# LTC4222.net
KiCad netlist of a schematic drawn in EAGLE
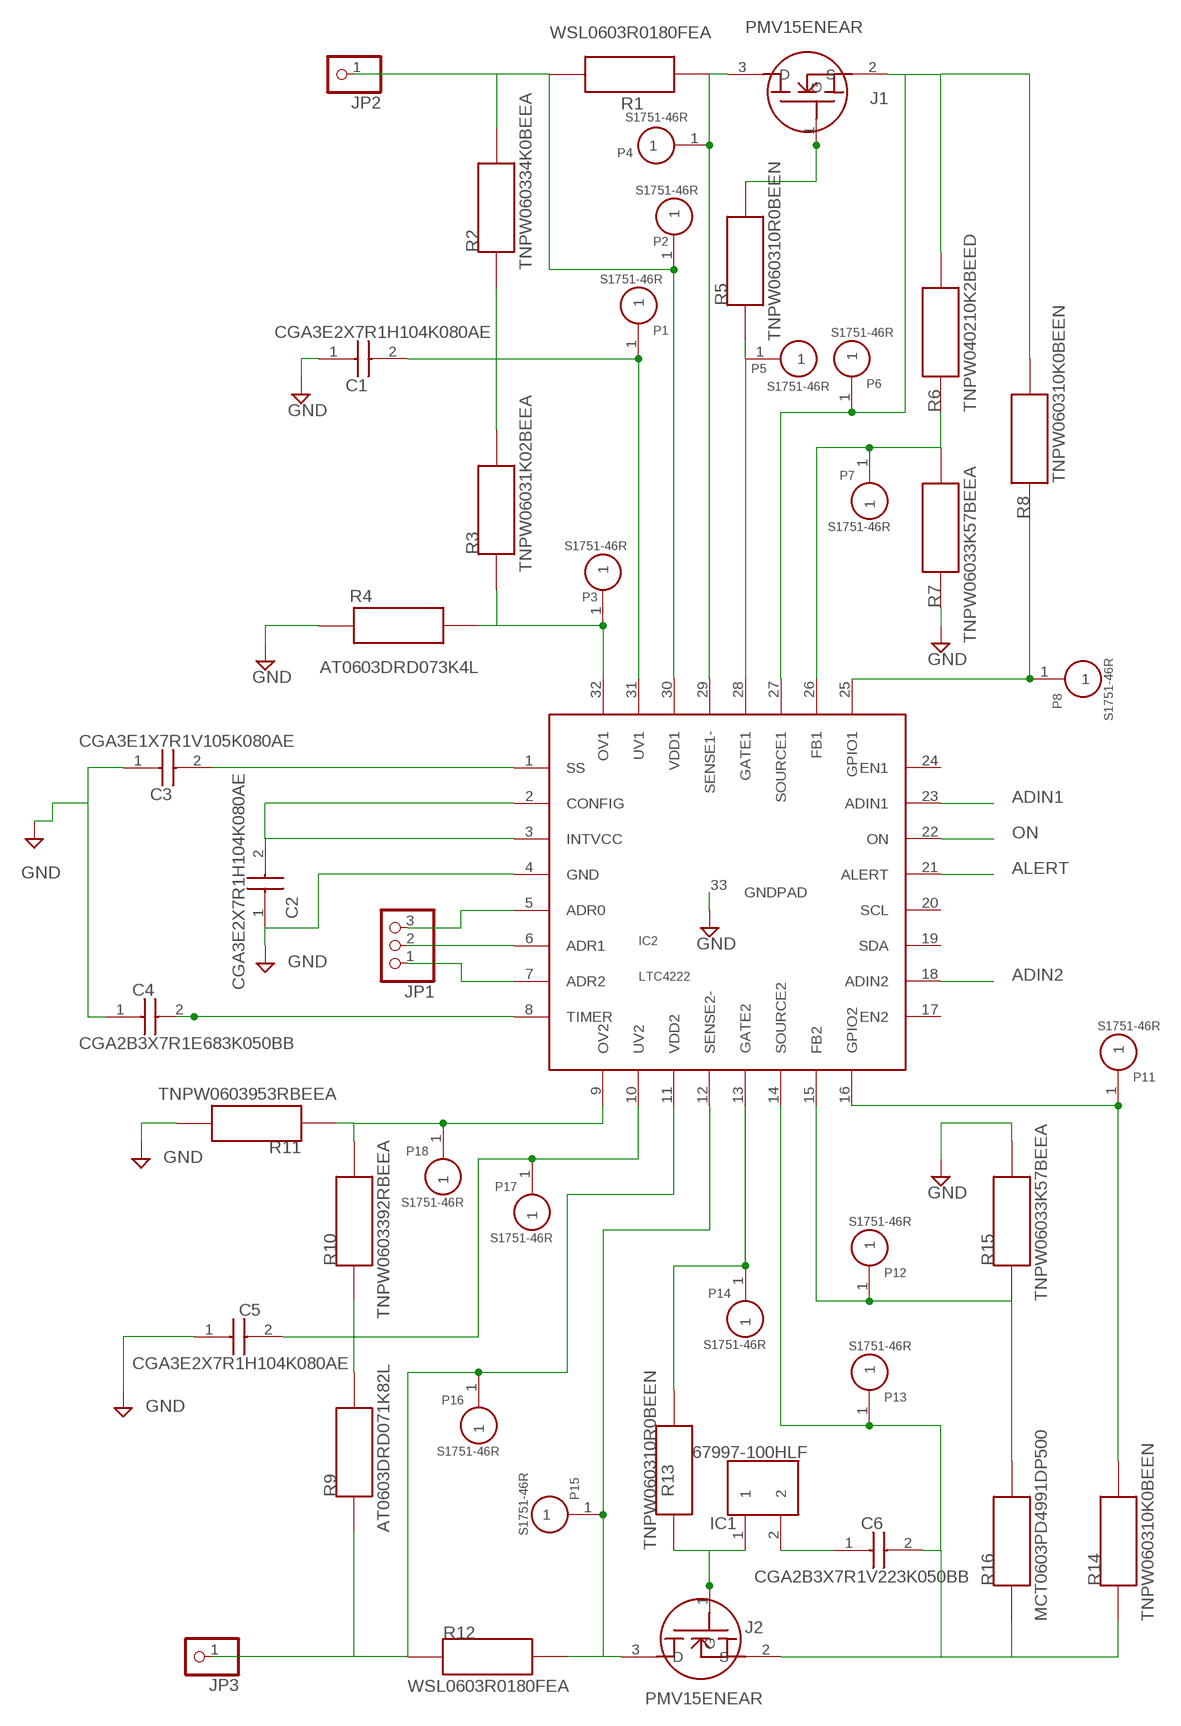
[diagram p0: schematic, sheet 1]

(export (version "E")
  (design (tool "Eeschema 10.0.6"))
  (components
    (comp (ref "C1")
      (value "CGA3E2X7R1H104K080AE")
      (footprint "eagle-import:CAPC1608X80M")
      (fields (field (name "MOUSER_PART_NUMBER") "810-CGA3E2X7R1H104KE"))
      (libsource (lib "eagle-import") (part "CGA3E2X7R1H104K080AE"))
    )
    (comp (ref "C2")
      (value "CGA3E2X7R1H104K080AE")
      (footprint "eagle-import:CAPC1608X80M")
      (fields (field (name "MOUSER_PART_NUMBER") "810-CGA3E2X7R1H104KE"))
      (libsource (lib "eagle-import") (part "CGA3E2X7R1H104K080AE"))
    )
    (comp (ref "C3")
      (value "CGA3E1X7R1V105K080AE")
      (footprint "eagle-import:CAPC1608X80M")
      (fields (field (name "MOUSER_PART_NUMBER") "810-CGA3E1X7R1V105KA"))
      (libsource (lib "eagle-import") (part "CGA3E1X7R1V105K080AE"))
    )
    (comp (ref "C4")
      (value "CGA2B3X7R1E683K050BB")
      (footprint "eagle-import:CAPC1005X50M")
      (fields (field (name "MOUSER_PART_NUMBER") "810-CGA2B3X7R1E683KB"))
      (libsource (lib "eagle-import") (part "CGA2B3X7R1E683K050BB"))
    )
    (comp (ref "C5")
      (value "CGA3E2X7R1H104K080AE")
      (footprint "eagle-import:CAPC1608X80M")
      (fields (field (name "MOUSER_PART_NUMBER") "810-CGA3E2X7R1H104KE"))
      (libsource (lib "eagle-import") (part "CGA3E2X7R1H104K080AE"))
    )
    (comp (ref "C6")
      (value "CGA2B3X7R1V223K050BB")
      (footprint "eagle-import:CAPC1005X50M")
      (fields (field (name "MOUSER_PART_NUMBER") "810-CGA2B3X7R1V223KB"))
      (libsource (lib "eagle-import") (part "CGA2B3X7R1V223K050BB"))
    )
    (comp (ref "IC1")
      (value "67997-100HLF")
      (footprint "eagle-import:HDRV2W64P254_2X1_241X508X838B")
      (fields (field (name "MOUSER_PART_NUMBER") "649-67997-100HLF"))
      (libsource (lib "eagle-import") (part "67997-100HLF"))
    )
    (comp (ref "IC2")
      (value "LTC4222")
      (footprint "eagle-import:QFN50P500X500X75-33T345M")
      (fields
        (field (name "MANUFACTURER_PART_NUMBER") "LTC4222CUH#PBF")
        (field (name "MOUSER_PART_NUMBER") "584-LTC4222CUH#PBF")
      )
      (libsource (lib "eagle-import") (part "LTC4222"))
    )
    (comp (ref "J1")
      (value "PMV15ENEAR")
      (footprint "eagle-import:SOT95P230X110-3M")
      (fields (field (name "MOUSER_PART_NUMBER") "771-PMV15ENEAR"))
      (libsource (lib "eagle-import") (part "PMV15ENEAR"))
    )
    (comp (ref "J2")
      (value "PMV15ENEAR")
      (footprint "eagle-import:SOT95P230X110-3M")
      (fields (field (name "MOUSER_PART_NUMBER") "771-PMV15ENEAR"))
      (libsource (lib "eagle-import") (part "PMV15ENEAR"))
    )
    (comp (ref "JP1")
      (value "PINHD-1X3")
      (footprint "eagle-import:1X03")
      (libsource (lib "eagle-import") (part "PINHD-1X3"))
    )
    (comp (ref "JP2")
      (value "PINHD-1X1")
      (footprint "eagle-import:1X01")
      (libsource (lib "eagle-import") (part "PINHD-1X1"))
    )
    (comp (ref "JP3")
      (value "PINHD-1X1")
      (footprint "eagle-import:1X01")
      (libsource (lib "eagle-import") (part "PINHD-1X1"))
    )
    (comp (ref "P1")
      (value "S1751-46R")
      (footprint "eagle-import:S1751-46R")
      (libsource (lib "eagle-import") (part "S1751-46R"))
    )
    (comp (ref "P2")
      (value "S1751-46R")
      (footprint "eagle-import:S1751-46R")
      (libsource (lib "eagle-import") (part "S1751-46R"))
    )
    (comp (ref "P3")
      (value "S1751-46R")
      (footprint "eagle-import:S1751-46R")
      (libsource (lib "eagle-import") (part "S1751-46R"))
    )
    (comp (ref "P4")
      (value "S1751-46R")
      (footprint "eagle-import:S1751-46R")
      (libsource (lib "eagle-import") (part "S1751-46R"))
    )
    (comp (ref "P5")
      (value "S1751-46R")
      (footprint "eagle-import:S1751-46R")
      (libsource (lib "eagle-import") (part "S1751-46R"))
    )
    (comp (ref "P6")
      (value "S1751-46R")
      (footprint "eagle-import:S1751-46R")
      (libsource (lib "eagle-import") (part "S1751-46R"))
    )
    (comp (ref "P7")
      (value "S1751-46R")
      (footprint "eagle-import:S1751-46R")
      (libsource (lib "eagle-import") (part "S1751-46R"))
    )
    (comp (ref "P8")
      (value "S1751-46R")
      (footprint "eagle-import:S1751-46R")
      (libsource (lib "eagle-import") (part "S1751-46R"))
    )
    (comp (ref "P11")
      (value "S1751-46R")
      (footprint "eagle-import:S1751-46R")
      (libsource (lib "eagle-import") (part "S1751-46R"))
    )
    (comp (ref "P12")
      (value "S1751-46R")
      (footprint "eagle-import:S1751-46R")
      (libsource (lib "eagle-import") (part "S1751-46R"))
    )
    (comp (ref "P13")
      (value "S1751-46R")
      (footprint "eagle-import:S1751-46R")
      (libsource (lib "eagle-import") (part "S1751-46R"))
    )
    (comp (ref "P14")
      (value "S1751-46R")
      (footprint "eagle-import:S1751-46R")
      (libsource (lib "eagle-import") (part "S1751-46R"))
    )
    (comp (ref "P15")
      (value "S1751-46R")
      (footprint "eagle-import:S1751-46R")
      (libsource (lib "eagle-import") (part "S1751-46R"))
    )
    (comp (ref "P16")
      (value "S1751-46R")
      (footprint "eagle-import:S1751-46R")
      (libsource (lib "eagle-import") (part "S1751-46R"))
    )
    (comp (ref "P17")
      (value "S1751-46R")
      (footprint "eagle-import:S1751-46R")
      (libsource (lib "eagle-import") (part "S1751-46R"))
    )
    (comp (ref "P18")
      (value "S1751-46R")
      (footprint "eagle-import:S1751-46R")
      (libsource (lib "eagle-import") (part "S1751-46R"))
    )
    (comp (ref "R1")
      (value "WSL0603R0180FEA")
      (footprint "eagle-import:RESC1507X40M")
      (fields (field (name "MOUSER_PART_NUMBER") "71-WSL0603R0180FEA"))
      (libsource (lib "eagle-import") (part "WSL0603R0180FEA"))
    )
    (comp (ref "R2")
      (value "TNPW060334K0BEEA")
      (footprint "eagle-import:AT0603")
      (fields
        (field (name "MANUFACTURER_PART_NUMBER") " TNPW060334K0BEEA")
        (field (name "MOUSER_PART_NUMBER") "71-TNPW060334K0BEEA")
      )
      (libsource (lib "eagle-import") (part "TNPW060334K0BEEA"))
    )
    (comp (ref "R3")
      (value "TNPW06031K02BEEA")
      (footprint "eagle-import:AT0603")
      (fields (field (name "MOUSER_PART_NUMBER") "71-TNPW06031K02BEEA"))
      (libsource (lib "eagle-import") (part "TNPW06031K02BEEA"))
    )
    (comp (ref "R4")
      (value "AT0603DRD073K4L")
      (footprint "eagle-import:RESC1608X45M")
      (fields (field (name "MOUSER_PART_NUMBER") "603-AT0603DRD073K4L"))
      (libsource (lib "eagle-import") (part "AT0603DRD073K4L"))
    )
    (comp (ref "R5")
      (value "TNPW060310R0BEEN")
      (footprint "eagle-import:AT0603")
      (fields (field (name "MOUSER_PART_NUMBER") "71-TNPW060310R0BEEN"))
      (libsource (lib "eagle-import") (part "TNPW060310R0BEEN"))
    )
    (comp (ref "R6")
      (value "TNPW040210K2BEED")
      (footprint "eagle-import:RESC1005X35M")
      (fields (field (name "MOUSER_PART_NUMBER") "71-TNPW040210K2BEED"))
      (libsource (lib "eagle-import") (part "TNPW040210K2BEED"))
    )
    (comp (ref "R7")
      (value "TNPW06033K57BEEA")
      (footprint "eagle-import:AT0603")
      (fields (field (name "MOUSER_PART_NUMBER") "71-TNPW06033K57BEEA"))
      (libsource (lib "eagle-import") (part "TNPW06033K57BEEA"))
    )
    (comp (ref "R8")
      (value "TNPW060310K0BEEN")
      (footprint "eagle-import:AT0603")
      (fields (field (name "MOUSER_PART_NUMBER") "71-TNPW060310K0BEEN"))
      (libsource (lib "eagle-import") (part "TNPW060310K0BEEN"))
    )
    (comp (ref "R9")
      (value "AT0603DRD071K82L")
      (footprint "eagle-import:RESC1608X45M")
      (fields (field (name "MOUSER_PART_NUMBER") "603-AT0603DRD071K82L"))
      (libsource (lib "eagle-import") (part "AT0603DRD071K82L"))
    )
    (comp (ref "R10")
      (value "TNPW0603392RBEEA")
      (footprint "eagle-import:AT0603")
      (fields (field (name "MOUSER_PART_NUMBER") "71-TNPW0603392RBEEA"))
      (libsource (lib "eagle-import") (part "TNPW0603392RBEEA"))
    )
    (comp (ref "R11")
      (value "TNPW0603953RBEEA")
      (footprint "eagle-import:AT0603")
      (fields (field (name "MOUSER_PART_NUMBER") "71-TNPW0603953RBEEA"))
      (libsource (lib "eagle-import") (part "TNPW0603953RBEEA"))
    )
    (comp (ref "R12")
      (value "WSL0603R0180FEA")
      (footprint "eagle-import:RESC1507X40M")
      (fields (field (name "MOUSER_PART_NUMBER") "71-WSL0603R0180FEA"))
      (libsource (lib "eagle-import") (part "WSL0603R0180FEA"))
    )
    (comp (ref "R13")
      (value "TNPW060310R0BEEN")
      (footprint "eagle-import:AT0603")
      (fields (field (name "MOUSER_PART_NUMBER") "71-TNPW060310R0BEEN"))
      (libsource (lib "eagle-import") (part "TNPW060310R0BEEN"))
    )
    (comp (ref "R14")
      (value "TNPW060310K0BEEN")
      (footprint "eagle-import:AT0603")
      (fields (field (name "MOUSER_PART_NUMBER") "71-TNPW060310K0BEEN"))
      (libsource (lib "eagle-import") (part "TNPW060310K0BEEN"))
    )
    (comp (ref "R15")
      (value "TNPW06033K57BEEA")
      (footprint "eagle-import:AT0603")
      (fields (field (name "MOUSER_PART_NUMBER") "71-TNPW06033K57BEEA"))
      (libsource (lib "eagle-import") (part "TNPW06033K57BEEA"))
    )
    (comp (ref "R16")
      (value "MCT0603PD4991DP500")
      (footprint "eagle-import:RESC1508X47M")
      (fields
        (field (name "MANUFACTURER_PART_NUMBER") " MCT0603PD4991DP500")
        (field (name "MOUSER_PART_NUMBER") "594-MCT0603PD4991DP5")
      )
      (libsource (lib "eagle-import") (part "MCT0603PD4991DP500"))
    )
  )
  (nets
    (net (code "1") (name "/ADIN1") (class "Default")
      (node (ref "IC2") (pin "23") (pinfunction "ADIN1_23") (pintype "bidirectional"))
    )
    (net (code "2") (name "/ADIN2") (class "Default")
      (node (ref "IC2") (pin "18") (pinfunction "ADIN2_18") (pintype "bidirectional"))
    )
    (net (code "3") (name "/ALERT") (class "Default")
      (node (ref "IC2") (pin "21") (pinfunction "ALERT_21") (pintype "bidirectional"))
    )
    (net (code "4") (name "/ON") (class "Default")
      (node (ref "IC2") (pin "22") (pinfunction "ON_22") (pintype "bidirectional"))
    )
    (net (code "5") (name "GND") (class "Default")
      (node (ref "C1") (pin "1") (pinfunction "1_1") (pintype "bidirectional"))
      (node (ref "C2") (pin "1") (pinfunction "1_1") (pintype "bidirectional"))
      (node (ref "C3") (pin "1") (pinfunction "1_1") (pintype "bidirectional"))
      (node (ref "C4") (pin "1") (pinfunction "1_1") (pintype "bidirectional"))
      (node (ref "C5") (pin "1") (pinfunction "1_1") (pintype "bidirectional"))
      (node (ref "IC2") (pin "4") (pinfunction "GND_4") (pintype "bidirectional"))
      (node (ref "R11") (pin "2") (pinfunction "P$2_2") (pintype "bidirectional"))
      (node (ref "R15") (pin "2") (pinfunction "P$2_2") (pintype "bidirectional"))
      (node (ref "R4") (pin "2") (pinfunction "P$2_2") (pintype "bidirectional"))
      (node (ref "R7") (pin "1") (pinfunction "P$1_1") (pintype "bidirectional"))
    )
    (net (code "6") (name "Net-(C6-Pad1)") (class "Default")
      (node (ref "C6") (pin "1") (pinfunction "1_1") (pintype "bidirectional"))
      (node (ref "IC1") (pin "2") (pinfunction "2_2") (pintype "bidirectional"))
    )
    (net (code "7") (name "Net-(IC2-ADR0)") (class "Default")
      (node (ref "IC2") (pin "5") (pinfunction "ADR0_5") (pintype "bidirectional"))
      (node (ref "JP1") (pin "3") (pinfunction "3_3") (pintype "passive"))
    )
    (net (code "8") (name "Net-(IC2-ADR1)") (class "Default")
      (node (ref "IC2") (pin "6") (pinfunction "ADR1_6") (pintype "bidirectional"))
      (node (ref "JP1") (pin "2") (pinfunction "2_2") (pintype "passive"))
    )
    (net (code "9") (name "Net-(IC2-ADR2)") (class "Default")
      (node (ref "IC2") (pin "7") (pinfunction "ADR2_7") (pintype "bidirectional"))
      (node (ref "JP1") (pin "1") (pinfunction "1_1") (pintype "passive"))
    )
    (net (code "10") (name "Net-(IC2-CONFIG)") (class "Default")
      (node (ref "C2") (pin "2") (pinfunction "2_2") (pintype "bidirectional"))
      (node (ref "IC2") (pin "2") (pinfunction "CONFIG_2") (pintype "bidirectional"))
      (node (ref "IC2") (pin "3") (pinfunction "INTVCC_3") (pintype "bidirectional"))
    )
    (net (code "11") (name "Net-(IC2-FB1)") (class "Default")
      (node (ref "IC2") (pin "26") (pinfunction "FB1_26") (pintype "bidirectional"))
      (node (ref "P7") (pin "1") (pinfunction "1_1") (pintype "bidirectional"))
      (node (ref "R6") (pin "1") (pinfunction "P$1_1") (pintype "bidirectional"))
      (node (ref "R7") (pin "2") (pinfunction "P$2_2") (pintype "bidirectional"))
    )
    (net (code "12") (name "Net-(IC2-FB2)") (class "Default")
      (node (ref "IC2") (pin "15") (pinfunction "FB2_15") (pintype "bidirectional"))
      (node (ref "P12") (pin "1") (pinfunction "1_1") (pintype "bidirectional"))
      (node (ref "R15") (pin "1") (pinfunction "P$1_1") (pintype "bidirectional"))
      (node (ref "R16") (pin "2") (pinfunction "P$2_2") (pintype "bidirectional"))
    )
    (net (code "13") (name "Net-(IC2-GATE1)") (class "Default")
      (node (ref "IC2") (pin "28") (pinfunction "GATE1_28") (pintype "bidirectional"))
      (node (ref "P5") (pin "1") (pinfunction "1_1") (pintype "bidirectional"))
      (node (ref "R5") (pin "1") (pinfunction "P$1_1") (pintype "bidirectional"))
    )
    (net (code "14") (name "Net-(IC2-GATE2)") (class "Default")
      (node (ref "IC2") (pin "13") (pinfunction "GATE2_13") (pintype "bidirectional"))
      (node (ref "P14") (pin "1") (pinfunction "1_1") (pintype "bidirectional"))
      (node (ref "R13") (pin "2") (pinfunction "P$2_2") (pintype "bidirectional"))
    )
    (net (code "15") (name "Net-(IC2-GPIO1)") (class "Default")
      (node (ref "IC2") (pin "25") (pinfunction "GPIO1_25") (pintype "bidirectional"))
      (node (ref "P8") (pin "1") (pinfunction "1_1") (pintype "bidirectional"))
      (node (ref "R8") (pin "1") (pinfunction "P$1_1") (pintype "bidirectional"))
    )
    (net (code "16") (name "Net-(IC2-GPIO2)") (class "Default")
      (node (ref "IC2") (pin "16") (pinfunction "GPIO2_16") (pintype "bidirectional"))
      (node (ref "P11") (pin "1") (pinfunction "1_1") (pintype "bidirectional"))
      (node (ref "R14") (pin "2") (pinfunction "P$2_2") (pintype "bidirectional"))
    )
    (net (code "17") (name "Net-(IC2-OV1)") (class "Default")
      (node (ref "IC2") (pin "32") (pinfunction "OV1_32") (pintype "bidirectional"))
      (node (ref "P3") (pin "1") (pinfunction "1_1") (pintype "bidirectional"))
      (node (ref "R3") (pin "1") (pinfunction "P$1_1") (pintype "bidirectional"))
      (node (ref "R4") (pin "1") (pinfunction "P$1_1") (pintype "bidirectional"))
    )
    (net (code "18") (name "Net-(IC2-OV2)") (class "Default")
      (node (ref "IC2") (pin "9") (pinfunction "OV2_9") (pintype "bidirectional"))
      (node (ref "P18") (pin "1") (pinfunction "1_1") (pintype "bidirectional"))
      (node (ref "R10") (pin "2") (pinfunction "P$2_2") (pintype "bidirectional"))
      (node (ref "R11") (pin "1") (pinfunction "P$1_1") (pintype "bidirectional"))
    )
    (net (code "19") (name "Net-(IC2-SENSE1-)") (class "Default")
      (node (ref "IC2") (pin "29") (pinfunction "SENSE1-_29") (pintype "bidirectional"))
      (node (ref "J1") (pin "3") (pinfunction "D_3") (pintype "bidirectional"))
      (node (ref "P4") (pin "1") (pinfunction "1_1") (pintype "bidirectional"))
      (node (ref "R1") (pin "2") (pinfunction "P$2_2") (pintype "bidirectional"))
    )
    (net (code "20") (name "Net-(IC2-SENSE2-)") (class "Default")
      (node (ref "IC2") (pin "12") (pinfunction "SENSE2-_12") (pintype "bidirectional"))
      (node (ref "J2") (pin "3") (pinfunction "D_3") (pintype "bidirectional"))
      (node (ref "P15") (pin "1") (pinfunction "1_1") (pintype "bidirectional"))
      (node (ref "R12") (pin "2") (pinfunction "P$2_2") (pintype "bidirectional"))
    )
    (net (code "21") (name "Net-(IC2-SOURCE1)") (class "Default")
      (node (ref "IC2") (pin "27") (pinfunction "SOURCE1_27") (pintype "bidirectional"))
      (node (ref "J1") (pin "2") (pinfunction "S_2") (pintype "bidirectional"))
      (node (ref "P6") (pin "1") (pinfunction "1_1") (pintype "bidirectional"))
      (node (ref "R6") (pin "2") (pinfunction "P$2_2") (pintype "bidirectional"))
      (node (ref "R8") (pin "2") (pinfunction "P$2_2") (pintype "bidirectional"))
    )
    (net (code "22") (name "Net-(IC2-SOURCE2)") (class "Default")
      (node (ref "C6") (pin "2") (pinfunction "2_2") (pintype "bidirectional"))
      (node (ref "IC2") (pin "14") (pinfunction "SOURCE2_14") (pintype "bidirectional"))
      (node (ref "J2") (pin "2") (pinfunction "S_2") (pintype "bidirectional"))
      (node (ref "P13") (pin "1") (pinfunction "1_1") (pintype "bidirectional"))
      (node (ref "R14") (pin "1") (pinfunction "P$1_1") (pintype "bidirectional"))
      (node (ref "R16") (pin "1") (pinfunction "P$1_1") (pintype "bidirectional"))
    )
    (net (code "23") (name "Net-(IC2-SS)") (class "Default")
      (node (ref "C3") (pin "2") (pinfunction "2_2") (pintype "bidirectional"))
      (node (ref "IC2") (pin "1") (pinfunction "SS_1") (pintype "bidirectional"))
    )
    (net (code "24") (name "Net-(IC2-TIMER)") (class "Default")
      (node (ref "C4") (pin "2") (pinfunction "2_2") (pintype "bidirectional"))
      (node (ref "IC2") (pin "8") (pinfunction "TIMER_8") (pintype "bidirectional"))
    )
    (net (code "25") (name "Net-(IC2-UV1)") (class "Default")
      (node (ref "C1") (pin "2") (pinfunction "2_2") (pintype "bidirectional"))
      (node (ref "IC2") (pin "31") (pinfunction "UV1_31") (pintype "bidirectional"))
      (node (ref "P1") (pin "1") (pinfunction "1_1") (pintype "bidirectional"))
      (node (ref "R2") (pin "1") (pinfunction "P$1_1") (pintype "bidirectional"))
      (node (ref "R3") (pin "2") (pinfunction "P$2_2") (pintype "bidirectional"))
    )
    (net (code "26") (name "Net-(IC2-UV2)") (class "Default")
      (node (ref "C5") (pin "2") (pinfunction "2_2") (pintype "bidirectional"))
      (node (ref "IC2") (pin "10") (pinfunction "UV2_10") (pintype "bidirectional"))
      (node (ref "P17") (pin "1") (pinfunction "1_1") (pintype "bidirectional"))
      (node (ref "R10") (pin "1") (pinfunction "P$1_1") (pintype "bidirectional"))
      (node (ref "R9") (pin "2") (pinfunction "P$2_2") (pintype "bidirectional"))
    )
    (net (code "27") (name "Net-(IC2-VDD1)") (class "Default")
      (node (ref "IC2") (pin "30") (pinfunction "VDD1_30") (pintype "bidirectional"))
      (node (ref "JP2") (pin "1") (pinfunction "1_1") (pintype "passive"))
      (node (ref "P2") (pin "1") (pinfunction "1_1") (pintype "bidirectional"))
      (node (ref "R1") (pin "1") (pinfunction "P$1_1") (pintype "bidirectional"))
      (node (ref "R2") (pin "2") (pinfunction "P$2_2") (pintype "bidirectional"))
    )
    (net (code "28") (name "Net-(IC2-VDD2)") (class "Default")
      (node (ref "IC2") (pin "11") (pinfunction "VDD2_11") (pintype "bidirectional"))
      (node (ref "JP3") (pin "1") (pinfunction "1_1") (pintype "passive"))
      (node (ref "P16") (pin "1") (pinfunction "1_1") (pintype "bidirectional"))
      (node (ref "R12") (pin "1") (pinfunction "P$1_1") (pintype "bidirectional"))
      (node (ref "R9") (pin "1") (pinfunction "P$1_1") (pintype "bidirectional"))
    )
    (net (code "29") (name "Net-(J1-G)") (class "Default")
      (node (ref "J1") (pin "1") (pinfunction "G_1") (pintype "bidirectional"))
      (node (ref "R5") (pin "2") (pinfunction "P$2_2") (pintype "bidirectional"))
    )
    (net (code "30") (name "Net-(J2-G)") (class "Default")
      (node (ref "IC1") (pin "1") (pinfunction "1_1") (pintype "bidirectional"))
      (node (ref "J2") (pin "1") (pinfunction "G_1") (pintype "bidirectional"))
      (node (ref "R13") (pin "1") (pinfunction "P$1_1") (pintype "bidirectional"))
    )
    (net (code "31") (name "unconnected-(IC2-EN1-Pad24)") (class "Default")
      (node (ref "IC2") (pin "24") (pinfunction "EN1_24") (pintype "bidirectional"))
    )
    (net (code "32") (name "unconnected-(IC2-EN2-Pad17)") (class "Default")
      (node (ref "IC2") (pin "17") (pinfunction "EN2_17") (pintype "bidirectional"))
    )
    (net (code "33") (name "unconnected-(IC2-GNDPAD-Pad33)") (class "Default")
      (node (ref "IC2") (pin "33") (pinfunction "GNDPAD_33") (pintype "bidirectional"))
    )
    (net (code "34") (name "unconnected-(IC2-SCL-Pad20)") (class "Default")
      (node (ref "IC2") (pin "20") (pinfunction "SCL_20") (pintype "bidirectional"))
    )
    (net (code "35") (name "unconnected-(IC2-SDA-Pad19)") (class "Default")
      (node (ref "IC2") (pin "19") (pinfunction "SDA_19") (pintype "bidirectional"))
    )
  )
)
